# Relay.net
KiCad netlist of a schematic drawn in Altium Designer
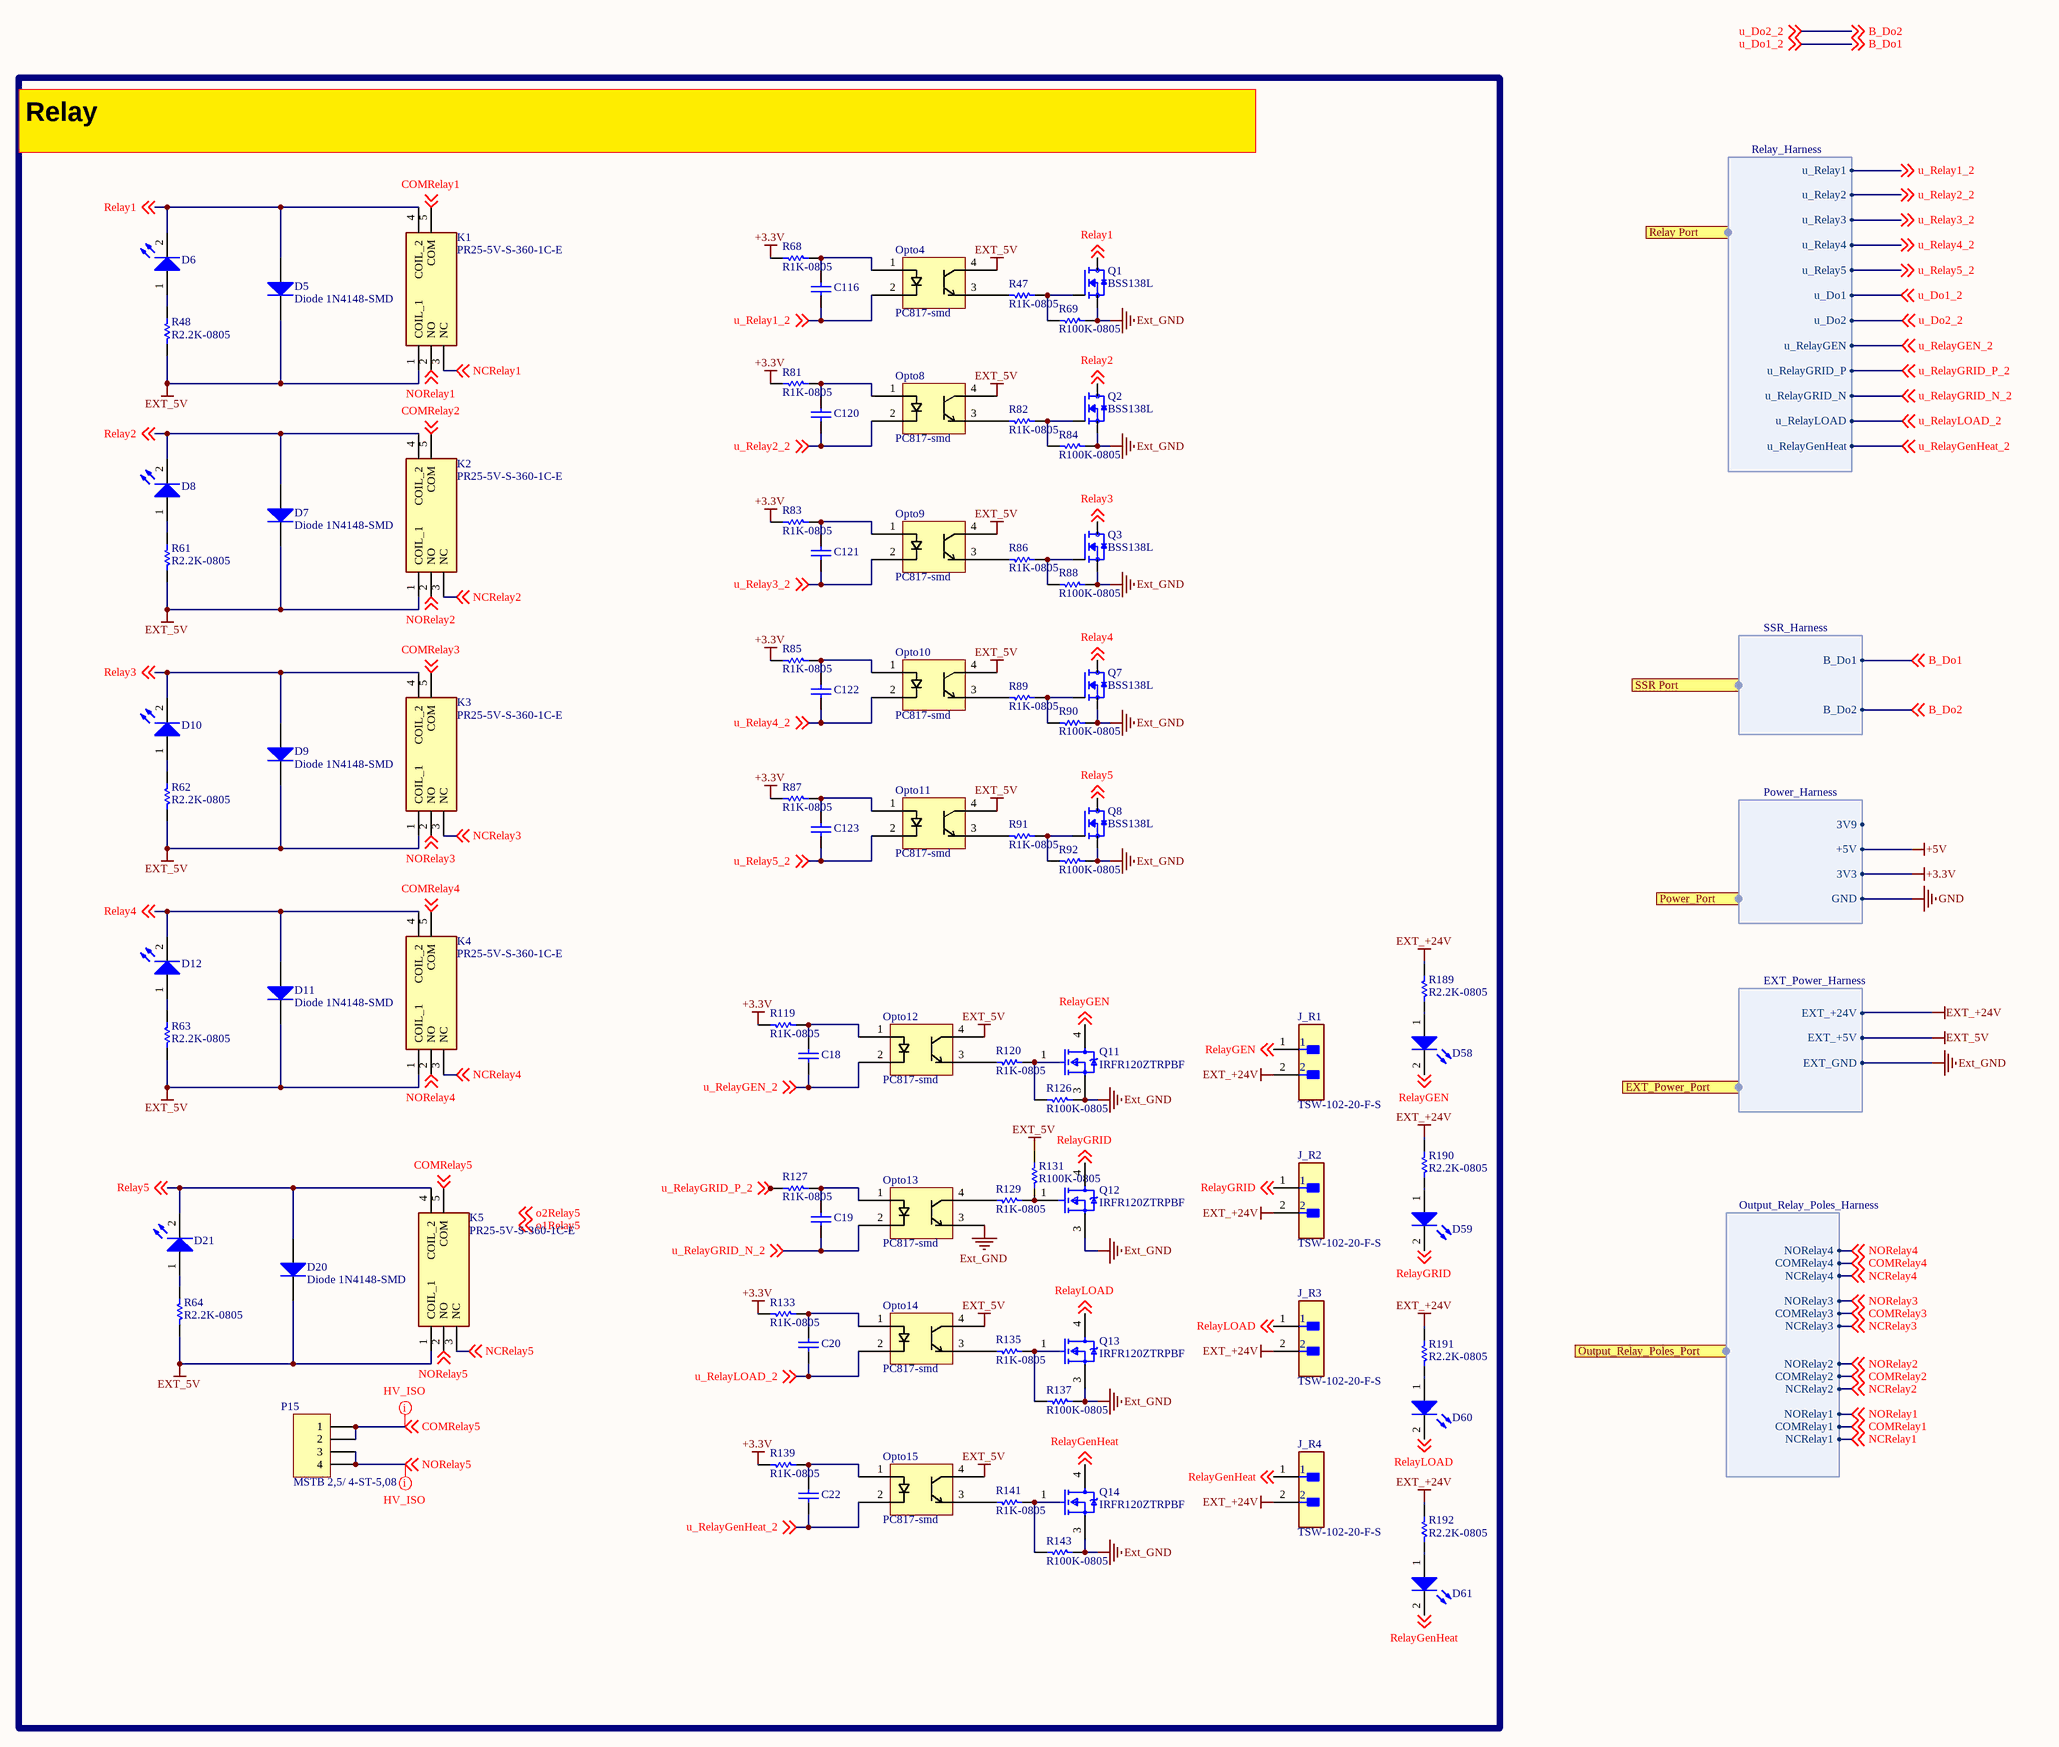
[diagram p0: Relay.SchDoc]

(export (version "E")
  (design (tool "Eeschema 10.0.6"))
  (components
    (comp (ref "C18")
      (value "~")
      (footprint "CRF06031")
      (description "Capacitor")
      (fields (field (name "DIGI-KEY_PART_NUMBER") "490-4789-1-ND"))
      (libsource (lib "Miscellaneous Devices") (part "Cap"))
    )
    (comp (ref "C19")
      (value "~")
      (footprint "CRF06031")
      (description "Capacitor")
      (fields (field (name "DIGI-KEY_PART_NUMBER") "490-4789-1-ND"))
      (libsource (lib "Miscellaneous Devices") (part "Cap"))
    )
    (comp (ref "C20")
      (value "~")
      (footprint "CRF06031")
      (description "Capacitor")
      (fields (field (name "DIGI-KEY_PART_NUMBER") "490-4789-1-ND"))
      (libsource (lib "Miscellaneous Devices") (part "Cap"))
    )
    (comp (ref "C22")
      (value "~")
      (footprint "CRF06031")
      (description "Capacitor")
      (fields (field (name "DIGI-KEY_PART_NUMBER") "490-4789-1-ND"))
      (libsource (lib "Miscellaneous Devices") (part "Cap"))
    )
    (comp (ref "C116")
      (value "~")
      (footprint "CRF06031")
      (description "Capacitor")
      (fields (field (name "DIGI-KEY_PART_NUMBER") "490-4789-1-ND"))
      (libsource (lib "Miscellaneous Devices") (part "Cap"))
    )
    (comp (ref "C120")
      (value "~")
      (footprint "CRF06031")
      (description "Capacitor")
      (fields (field (name "DIGI-KEY_PART_NUMBER") "490-4789-1-ND"))
      (libsource (lib "Miscellaneous Devices") (part "Cap"))
    )
    (comp (ref "C121")
      (value "~")
      (footprint "CRF06031")
      (description "Capacitor")
      (fields (field (name "DIGI-KEY_PART_NUMBER") "490-4789-1-ND"))
      (libsource (lib "Miscellaneous Devices") (part "Cap"))
    )
    (comp (ref "C122")
      (value "~")
      (footprint "CRF06031")
      (description "Capacitor")
      (fields (field (name "DIGI-KEY_PART_NUMBER") "490-4789-1-ND"))
      (libsource (lib "Miscellaneous Devices") (part "Cap"))
    )
    (comp (ref "C123")
      (value "~")
      (footprint "CRF06031")
      (description "Capacitor")
      (fields (field (name "DIGI-KEY_PART_NUMBER") "490-4789-1-ND"))
      (libsource (lib "Miscellaneous Devices") (part "Cap"))
    )
    (comp (ref "D5")
      (value "Diode 1N4148-SMD")
      (footprint "d1206")
      (description "1 Amp Fast Recovery Rectifier")
      (fields (field (name "DIGI-KEY_PART_NUMBER") "1N4148WSFSTR-ND"))
      (libsource (lib "Miscellaneous Devices") (part "Diode 1N4934"))
    )
    (comp (ref "D6")
      (value "LED_0805_green")
      (footprint "0805-LED")
      (libsource (lib "HosseinLib") (part "LED_0805"))
    )
    (comp (ref "D7")
      (value "Diode 1N4148-SMD")
      (footprint "d1206")
      (description "1 Amp Fast Recovery Rectifier")
      (fields (field (name "DIGI-KEY_PART_NUMBER") "1N4148WSFSTR-ND"))
      (libsource (lib "Miscellaneous Devices") (part "Diode 1N4934"))
    )
    (comp (ref "D8")
      (value "LED_0805_green")
      (footprint "0805-LED")
      (libsource (lib "HosseinLib") (part "LED_0805"))
    )
    (comp (ref "D9")
      (value "Diode 1N4148-SMD")
      (footprint "d1206")
      (description "1 Amp Fast Recovery Rectifier")
      (fields (field (name "DIGI-KEY_PART_NUMBER") "1N4148WSFSTR-ND"))
      (libsource (lib "Miscellaneous Devices") (part "Diode 1N4934"))
    )
    (comp (ref "D10")
      (value "LED_0805_green")
      (footprint "0805-LED")
      (libsource (lib "HosseinLib") (part "LED_0805"))
    )
    (comp (ref "D11")
      (value "Diode 1N4148-SMD")
      (footprint "d1206")
      (description "1 Amp Fast Recovery Rectifier")
      (fields (field (name "DIGI-KEY_PART_NUMBER") "1N4148WSFSTR-ND"))
      (libsource (lib "Miscellaneous Devices") (part "Diode 1N4934"))
    )
    (comp (ref "D12")
      (value "LED_0805_green")
      (footprint "0805-LED")
      (libsource (lib "HosseinLib") (part "LED_0805"))
    )
    (comp (ref "D20")
      (value "Diode 1N4148-SMD")
      (footprint "d1206")
      (description "1 Amp Fast Recovery Rectifier")
      (fields (field (name "DIGI-KEY_PART_NUMBER") "1N4148WSFSTR-ND"))
      (libsource (lib "Miscellaneous Devices") (part "Diode 1N4934"))
    )
    (comp (ref "D21")
      (value "LED_0805_green")
      (footprint "0805-LED")
      (libsource (lib "HosseinLib") (part "LED_0805"))
    )
    (comp (ref "D58")
      (value "LED_0805_green")
      (footprint "0805-LED")
      (libsource (lib "HosseinLib") (part "LED_0805"))
    )
    (comp (ref "D59")
      (value "LED_0805_green")
      (footprint "0805-LED")
      (libsource (lib "HosseinLib") (part "LED_0805"))
    )
    (comp (ref "D60")
      (value "LED_0805_green")
      (footprint "0805-LED")
      (libsource (lib "HosseinLib") (part "LED_0805"))
    )
    (comp (ref "D61")
      (value "LED_0805_green")
      (footprint "0805-LED")
      (libsource (lib "HosseinLib") (part "LED_0805"))
    )
    (comp (ref "J_R1")
      (value "TSW-102-20-F-S")
      (footprint "FP-TSW-102-12-T-S-MFG")
      (description "CONN HEADER VERT 2POS 2.54MM")
      (fields (field (name "DIGI-KEY_PART_NUMBER") "TSW-102-20-F-S-ND"))
      (libsource (lib "Components - 15.12.24 - 09.04") (part "CMP-02766-001444-1"))
    )
    (comp (ref "J_R2")
      (value "TSW-102-20-F-S")
      (footprint "FP-TSW-102-12-T-S-MFG")
      (description "CONN HEADER VERT 2POS 2.54MM")
      (fields (field (name "DIGI-KEY_PART_NUMBER") "TSW-102-20-F-S-ND"))
      (libsource (lib "Components - 15.12.24 - 09.04") (part "CMP-02766-001444-1"))
    )
    (comp (ref "J_R3")
      (value "TSW-102-20-F-S")
      (footprint "FP-TSW-102-12-T-S-MFG")
      (description "CONN HEADER VERT 2POS 2.54MM")
      (fields (field (name "DIGI-KEY_PART_NUMBER") "TSW-102-20-F-S-ND"))
      (libsource (lib "Components - 15.12.24 - 09.04") (part "CMP-02766-001444-1"))
    )
    (comp (ref "J_R4")
      (value "TSW-102-20-F-S")
      (footprint "FP-TSW-102-12-T-S-MFG")
      (description "CONN HEADER VERT 2POS 2.54MM")
      (fields (field (name "DIGI-KEY_PART_NUMBER") "TSW-102-20-F-S-ND"))
      (libsource (lib "Components - 15.12.24 - 09.04") (part "CMP-02766-001444-1"))
    )
    (comp (ref "K1")
      (value "PR25-5V-S-360-1C-E")
      (footprint "SamacSys:PR255VS3601CE")
      (description "Relay or Contactor")
      (fields
        (field (name "MOUSER PART NUMBER") "179-PR255VS3601CE")
        (field (name "DIGI-KEY_PART_NUMBER") "2223-PR25-5V-S-360-1C-E-ND")
      )
      (libsource (lib "*") (part "PR25-5V-S-360-1C-E"))
    )
    (comp (ref "K2")
      (value "PR25-5V-S-360-1C-E")
      (footprint "SamacSys:PR255VS3601CE")
      (description "Relay or Contactor")
      (fields
        (field (name "MOUSER PART NUMBER") "179-PR255VS3601CE")
        (field (name "DIGI-KEY_PART_NUMBER") "2223-PR25-5V-S-360-1C-E-ND")
      )
      (libsource (lib "*") (part "PR25-5V-S-360-1C-E"))
    )
    (comp (ref "K3")
      (value "PR25-5V-S-360-1C-E")
      (footprint "SamacSys:PR255VS3601CE")
      (description "Relay or Contactor")
      (fields
        (field (name "MOUSER PART NUMBER") "179-PR255VS3601CE")
        (field (name "DIGI-KEY_PART_NUMBER") "2223-PR25-5V-S-360-1C-E-ND")
      )
      (libsource (lib "*") (part "PR25-5V-S-360-1C-E"))
    )
    (comp (ref "K4")
      (value "PR25-5V-S-360-1C-E")
      (footprint "SamacSys:PR255VS3601CE")
      (description "Relay or Contactor")
      (fields
        (field (name "MOUSER PART NUMBER") "179-PR255VS3601CE")
        (field (name "DIGI-KEY_PART_NUMBER") "2223-PR25-5V-S-360-1C-E-ND")
      )
      (libsource (lib "*") (part "PR25-5V-S-360-1C-E"))
    )
    (comp (ref "K5")
      (value "PR25-5V-S-360-1C-E")
      (footprint "SamacSys:PR255VS3601CE")
      (description "Relay or Contactor")
      (fields
        (field (name "MOUSER PART NUMBER") "179-PR255VS3601CE")
        (field (name "DIGI-KEY_PART_NUMBER") "2223-PR25-5V-S-360-1C-E-ND")
      )
      (libsource (lib "*") (part "PR25-5V-S-360-1C-E"))
    )
    (comp (ref "Opto4")
      (value "PC817-smd")
      (footprint "PC817_SMD1")
      (fields (field (name "DIGI-KEY_PART_NUMBER") "2007-APC-817D1-SLTR-ND"))
      (libsource (lib "Almas Co") (part "PC817"))
    )
    (comp (ref "Opto8")
      (value "PC817-smd")
      (footprint "PC817_SMD1")
      (fields (field (name "DIGI-KEY_PART_NUMBER") "2007-APC-817D1-SLTR-ND"))
      (libsource (lib "Almas Co") (part "PC817"))
    )
    (comp (ref "Opto9")
      (value "PC817-smd")
      (footprint "PC817_SMD1")
      (fields (field (name "DIGI-KEY_PART_NUMBER") "2007-APC-817D1-SLTR-ND"))
      (libsource (lib "Almas Co") (part "PC817"))
    )
    (comp (ref "Opto10")
      (value "PC817-smd")
      (footprint "PC817_SMD1")
      (fields (field (name "DIGI-KEY_PART_NUMBER") "2007-APC-817D1-SLTR-ND"))
      (libsource (lib "Almas Co") (part "PC817"))
    )
    (comp (ref "Opto11")
      (value "PC817-smd")
      (footprint "PC817_SMD1")
      (fields (field (name "DIGI-KEY_PART_NUMBER") "2007-APC-817D1-SLTR-ND"))
      (libsource (lib "Almas Co") (part "PC817"))
    )
    (comp (ref "Opto12")
      (value "PC817-smd")
      (footprint "PC817_SMD1")
      (fields (field (name "DIGI-KEY_PART_NUMBER") "2007-APC-817D1-SLTR-ND"))
      (libsource (lib "Almas Co") (part "PC817"))
    )
    (comp (ref "Opto13")
      (value "PC817-smd")
      (footprint "PC817_SMD1")
      (fields (field (name "DIGI-KEY_PART_NUMBER") "2007-APC-817D1-SLTR-ND"))
      (libsource (lib "Almas Co") (part "PC817"))
    )
    (comp (ref "Opto14")
      (value "PC817-smd")
      (footprint "PC817_SMD1")
      (fields (field (name "DIGI-KEY_PART_NUMBER") "2007-APC-817D1-SLTR-ND"))
      (libsource (lib "Almas Co") (part "PC817"))
    )
    (comp (ref "Opto15")
      (value "PC817-smd")
      (footprint "PC817_SMD1")
      (fields (field (name "DIGI-KEY_PART_NUMBER") "2007-APC-817D1-SLTR-ND"))
      (libsource (lib "Almas Co") (part "PC817"))
    )
    (comp (ref "P15")
      (value "MSTB 2,5/ 4-ST-5,08")
      (footprint "MSTB 2,5/4-G-5,08")
      (description "Conn Phonix,4 Pitch: 5.08 mm")
      (fields (field (name "DIGI-KEY_PART_NUMBER") "277-1108-ND"))
      (libsource (lib "chilla bord") (part "Header 4"))
    )
    (comp (ref "Q1")
      (value "BSS138L")
      (footprint "BSS138L")
      (description "smd")
      (fields (field (name "MF") "ON Semiconductor") (field (name "DIGI-KEY_PART_NUMBER") "BSS138LTR-ND"))
      (libsource (lib "BSS138L") (part "BSS138L"))
    )
    (comp (ref "Q2")
      (value "BSS138L")
      (footprint "BSS138L")
      (description "smd")
      (fields (field (name "MF") "ON Semiconductor") (field (name "DIGI-KEY_PART_NUMBER") "BSS138LTR-ND"))
      (libsource (lib "BSS138L") (part "BSS138L"))
    )
    (comp (ref "Q3")
      (value "BSS138L")
      (footprint "BSS138L")
      (description "smd")
      (fields (field (name "MF") "ON Semiconductor") (field (name "DIGI-KEY_PART_NUMBER") "BSS138LTR-ND"))
      (libsource (lib "BSS138L") (part "BSS138L"))
    )
    (comp (ref "Q7")
      (value "BSS138L")
      (footprint "BSS138L")
      (description "smd")
      (fields (field (name "MF") "ON Semiconductor") (field (name "DIGI-KEY_PART_NUMBER") "BSS138LTR-ND"))
      (libsource (lib "BSS138L") (part "BSS138L"))
    )
    (comp (ref "Q8")
      (value "BSS138L")
      (footprint "BSS138L")
      (description "smd")
      (fields (field (name "MF") "ON Semiconductor") (field (name "DIGI-KEY_PART_NUMBER") "BSS138LTR-ND"))
      (libsource (lib "BSS138L") (part "BSS138L"))
    )
    (comp (ref "Q11")
      (value "IRFR120ZTRPBF")
      (footprint "FP-PG-TO252-3-MFG")
      (description "MOSFET N-CH 100V 8.7A DPAK")
      (fields (field (name "DIGI-KEY_PART_NUMBER") "IRFR120ZTRPBFTR-ND"))
      (libsource (lib "Altium Content Vault") (part "880dca94e4e73acafd9c8cab4fdbffa"))
    )
    (comp (ref "Q12")
      (value "IRFR120ZTRPBF")
      (footprint "FP-PG-TO252-3-MFG")
      (description "MOSFET N-CH 100V 8.7A DPAK")
      (fields (field (name "DIGI-KEY_PART_NUMBER") "IRFR120ZTRPBFTR-ND"))
      (libsource (lib "Altium Content Vault") (part "880dca94e4e73acafd9c8cab4fdbffa"))
    )
    (comp (ref "Q13")
      (value "IRFR120ZTRPBF")
      (footprint "FP-PG-TO252-3-MFG")
      (description "MOSFET N-CH 100V 8.7A DPAK")
      (fields (field (name "DIGI-KEY_PART_NUMBER") "IRFR120ZTRPBFTR-ND"))
      (libsource (lib "Altium Content Vault") (part "880dca94e4e73acafd9c8cab4fdbffa"))
    )
    (comp (ref "Q14")
      (value "IRFR120ZTRPBF")
      (footprint "FP-PG-TO252-3-MFG")
      (description "MOSFET N-CH 100V 8.7A DPAK")
      (fields (field (name "DIGI-KEY_PART_NUMBER") "IRFR120ZTRPBFTR-ND"))
      (libsource (lib "Altium Content Vault") (part "880dca94e4e73acafd9c8cab4fdbffa"))
    )
    (comp (ref "R47")
      (value "R1K-0805")
      (footprint "CRF06031")
      (description "Resistor")
      (fields (field (name "DIGI-KEY_PART_NUMBER") "311-1.00KCRTR-ND"))
      (libsource (lib "Miscellaneous Devices") (part "Res1"))
    )
    (comp (ref "R48")
      (value "R2.2K-0805")
      (footprint "CRF06031")
      (description "Resistor")
      (fields (field (name "DIGI-KEY_PART_NUMBER") "311-2.20KCRTR-ND"))
      (libsource (lib "Miscellaneous Devices") (part "Res1"))
    )
    (comp (ref "R61")
      (value "R2.2K-0805")
      (footprint "CRF06031")
      (description "Resistor")
      (fields (field (name "DIGI-KEY_PART_NUMBER") "311-2.20KCRTR-ND"))
      (libsource (lib "Miscellaneous Devices") (part "Res1"))
    )
    (comp (ref "R62")
      (value "R2.2K-0805")
      (footprint "CRF06031")
      (description "Resistor")
      (fields (field (name "DIGI-KEY_PART_NUMBER") "311-2.20KCRTR-ND"))
      (libsource (lib "Miscellaneous Devices") (part "Res1"))
    )
    (comp (ref "R63")
      (value "R2.2K-0805")
      (footprint "CRF06031")
      (description "Resistor")
      (fields (field (name "DIGI-KEY_PART_NUMBER") "311-2.20KCRTR-ND"))
      (libsource (lib "Miscellaneous Devices") (part "Res1"))
    )
    (comp (ref "R64")
      (value "R2.2K-0805")
      (footprint "CRF06031")
      (description "Resistor")
      (fields (field (name "DIGI-KEY_PART_NUMBER") "311-2.20KCRTR-ND"))
      (libsource (lib "Miscellaneous Devices") (part "Res1"))
    )
    (comp (ref "R68")
      (value "R1K-0805")
      (footprint "CRF06031")
      (description "Resistor")
      (fields (field (name "DIGI-KEY_PART_NUMBER") "311-1.00KCRTR-ND"))
      (libsource (lib "Miscellaneous Devices") (part "Res1"))
    )
    (comp (ref "R69")
      (value "R100K-0805")
      (footprint "CRF06031")
      (description "Resistor")
      (fields (field (name "DIGI-KEY_PART_NUMBER") "311-100KCRTR-ND"))
      (libsource (lib "Miscellaneous Devices") (part "Res1"))
    )
    (comp (ref "R81")
      (value "R1K-0805")
      (footprint "CRF06031")
      (description "Resistor")
      (fields (field (name "DIGI-KEY_PART_NUMBER") "311-1.00KCRTR-ND"))
      (libsource (lib "Miscellaneous Devices") (part "Res1"))
    )
    (comp (ref "R82")
      (value "R1K-0805")
      (footprint "CRF06031")
      (description "Resistor")
      (fields (field (name "DIGI-KEY_PART_NUMBER") "311-1.00KCRTR-ND"))
      (libsource (lib "Miscellaneous Devices") (part "Res1"))
    )
    (comp (ref "R83")
      (value "R1K-0805")
      (footprint "CRF06031")
      (description "Resistor")
      (fields (field (name "DIGI-KEY_PART_NUMBER") "311-1.00KCRTR-ND"))
      (libsource (lib "Miscellaneous Devices") (part "Res1"))
    )
    (comp (ref "R84")
      (value "R100K-0805")
      (footprint "CRF06031")
      (description "Resistor")
      (fields (field (name "DIGI-KEY_PART_NUMBER") "311-100KCRTR-ND"))
      (libsource (lib "Miscellaneous Devices") (part "Res1"))
    )
    (comp (ref "R85")
      (value "R1K-0805")
      (footprint "CRF06031")
      (description "Resistor")
      (fields (field (name "DIGI-KEY_PART_NUMBER") "311-1.00KCRTR-ND"))
      (libsource (lib "Miscellaneous Devices") (part "Res1"))
    )
    (comp (ref "R86")
      (value "R1K-0805")
      (footprint "CRF06031")
      (description "Resistor")
      (fields (field (name "DIGI-KEY_PART_NUMBER") "311-1.00KCRTR-ND"))
      (libsource (lib "Miscellaneous Devices") (part "Res1"))
    )
    (comp (ref "R87")
      (value "R1K-0805")
      (footprint "CRF06031")
      (description "Resistor")
      (fields (field (name "DIGI-KEY_PART_NUMBER") "311-1.00KCRTR-ND"))
      (libsource (lib "Miscellaneous Devices") (part "Res1"))
    )
    (comp (ref "R88")
      (value "R100K-0805")
      (footprint "CRF06031")
      (description "Resistor")
      (fields (field (name "DIGI-KEY_PART_NUMBER") "311-100KCRTR-ND"))
      (libsource (lib "Miscellaneous Devices") (part "Res1"))
    )
    (comp (ref "R89")
      (value "R1K-0805")
      (footprint "CRF06031")
      (description "Resistor")
      (fields (field (name "DIGI-KEY_PART_NUMBER") "311-1.00KCRTR-ND"))
      (libsource (lib "Miscellaneous Devices") (part "Res1"))
    )
    (comp (ref "R90")
      (value "R100K-0805")
      (footprint "CRF06031")
      (description "Resistor")
      (fields (field (name "DIGI-KEY_PART_NUMBER") "311-100KCRTR-ND"))
      (libsource (lib "Miscellaneous Devices") (part "Res1"))
    )
    (comp (ref "R91")
      (value "R1K-0805")
      (footprint "CRF06031")
      (description "Resistor")
      (fields (field (name "DIGI-KEY_PART_NUMBER") "311-1.00KCRTR-ND"))
      (libsource (lib "Miscellaneous Devices") (part "Res1"))
    )
    (comp (ref "R92")
      (value "R100K-0805")
      (footprint "CRF06031")
      (description "Resistor")
      (fields (field (name "DIGI-KEY_PART_NUMBER") "311-100KCRTR-ND"))
      (libsource (lib "Miscellaneous Devices") (part "Res1"))
    )
    (comp (ref "R119")
      (value "R1K-0805")
      (footprint "CRF06031")
      (description "Resistor")
      (fields (field (name "DIGI-KEY_PART_NUMBER") "311-1.00KCRTR-ND"))
      (libsource (lib "Miscellaneous Devices") (part "Res1"))
    )
    (comp (ref "R120")
      (value "R1K-0805")
      (footprint "CRF06031")
      (description "Resistor")
      (fields (field (name "DIGI-KEY_PART_NUMBER") "311-1.00KCRTR-ND"))
      (libsource (lib "Miscellaneous Devices") (part "Res1"))
    )
    (comp (ref "R126")
      (value "R100K-0805")
      (footprint "CRF06031")
      (description "Resistor")
      (fields (field (name "DIGI-KEY_PART_NUMBER") "311-100KCRTR-ND"))
      (libsource (lib "Miscellaneous Devices") (part "Res1"))
    )
    (comp (ref "R127")
      (value "R1K-0805")
      (footprint "CRF06031")
      (description "Resistor")
      (fields (field (name "DIGI-KEY_PART_NUMBER") "311-1.00KCRTR-ND"))
      (libsource (lib "Miscellaneous Devices") (part "Res1"))
    )
    (comp (ref "R129")
      (value "R1K-0805")
      (footprint "CRF06031")
      (description "Resistor")
      (fields (field (name "DIGI-KEY_PART_NUMBER") "311-1.00KCRTR-ND"))
      (libsource (lib "Miscellaneous Devices") (part "Res1"))
    )
    (comp (ref "R131")
      (value "R100K-0805")
      (footprint "CRF06031")
      (description "Resistor")
      (fields (field (name "DIGI-KEY_PART_NUMBER") "311-100KCRTR-ND"))
      (libsource (lib "Miscellaneous Devices") (part "Res1"))
    )
    (comp (ref "R133")
      (value "R1K-0805")
      (footprint "CRF06031")
      (description "Resistor")
      (fields (field (name "DIGI-KEY_PART_NUMBER") "311-1.00KCRTR-ND"))
      (libsource (lib "Miscellaneous Devices") (part "Res1"))
    )
    (comp (ref "R135")
      (value "R1K-0805")
      (footprint "CRF06031")
      (description "Resistor")
      (fields (field (name "DIGI-KEY_PART_NUMBER") "311-1.00KCRTR-ND"))
      (libsource (lib "Miscellaneous Devices") (part "Res1"))
    )
    (comp (ref "R137")
      (value "R100K-0805")
      (footprint "CRF06031")
      (description "Resistor")
      (fields (field (name "DIGI-KEY_PART_NUMBER") "311-100KCRTR-ND"))
      (libsource (lib "Miscellaneous Devices") (part "Res1"))
    )
    (comp (ref "R139")
      (value "R1K-0805")
      (footprint "CRF06031")
      (description "Resistor")
      (fields (field (name "DIGI-KEY_PART_NUMBER") "311-1.00KCRTR-ND"))
      (libsource (lib "Miscellaneous Devices") (part "Res1"))
    )
    (comp (ref "R141")
      (value "R1K-0805")
      (footprint "CRF06031")
      (description "Resistor")
      (fields (field (name "DIGI-KEY_PART_NUMBER") "311-1.00KCRTR-ND"))
      (libsource (lib "Miscellaneous Devices") (part "Res1"))
    )
    (comp (ref "R143")
      (value "R100K-0805")
      (footprint "CRF06031")
      (description "Resistor")
      (fields (field (name "DIGI-KEY_PART_NUMBER") "311-100KCRTR-ND"))
      (libsource (lib "Miscellaneous Devices") (part "Res1"))
    )
    (comp (ref "R189")
      (value "R2.2K-0805")
      (footprint "CRF06031")
      (description "Resistor")
      (fields (field (name "DIGI-KEY_PART_NUMBER") "311-2.20KCRTR-ND"))
      (libsource (lib "Miscellaneous Devices") (part "Res1"))
    )
    (comp (ref "R190")
      (value "R2.2K-0805")
      (footprint "CRF06031")
      (description "Resistor")
      (fields (field (name "DIGI-KEY_PART_NUMBER") "311-2.20KCRTR-ND"))
      (libsource (lib "Miscellaneous Devices") (part "Res1"))
    )
    (comp (ref "R191")
      (value "R2.2K-0805")
      (footprint "CRF06031")
      (description "Resistor")
      (fields (field (name "DIGI-KEY_PART_NUMBER") "311-2.20KCRTR-ND"))
      (libsource (lib "Miscellaneous Devices") (part "Res1"))
    )
    (comp (ref "R192")
      (value "R2.2K-0805")
      (footprint "CRF06031")
      (description "Resistor")
      (fields (field (name "DIGI-KEY_PART_NUMBER") "311-2.20KCRTR-ND"))
      (libsource (lib "Miscellaneous Devices") (part "Res1"))
    )
  )
  (nets
    (net (code "6") (name "+3.3V") (class "Default")
      (node (ref "R119") (pin "2") (pinfunction "2_2") (pintype "passive"))
      (node (ref "R133") (pin "2") (pinfunction "2_2") (pintype "passive"))
      (node (ref "R139") (pin "2") (pinfunction "2_2") (pintype "passive"))
      (node (ref "R68") (pin "2") (pinfunction "2_2") (pintype "passive"))
      (node (ref "R81") (pin "2") (pinfunction "2_2") (pintype "passive"))
      (node (ref "R83") (pin "2") (pinfunction "2_2") (pintype "passive"))
      (node (ref "R85") (pin "2") (pinfunction "2_2") (pintype "passive"))
      (node (ref "R87") (pin "2") (pinfunction "2_2") (pintype "passive"))
    )
    (net (code "15") (name "COMRelay1") (class "Default")
      (node (ref "K1") (pin "5") (pinfunction "COM_5") (pintype "passive"))
    )
    (net (code "16") (name "COMRelay2") (class "Default")
      (node (ref "K2") (pin "5") (pinfunction "COM_5") (pintype "passive"))
    )
    (net (code "17") (name "COMRelay3") (class "Default")
      (node (ref "K3") (pin "5") (pinfunction "COM_5") (pintype "passive"))
    )
    (net (code "18") (name "COMRelay4") (class "Default")
      (node (ref "K4") (pin "5") (pinfunction "COM_5") (pintype "passive"))
    )
    (net (code "19") (name "COMRelay5") (class "Default")
      (node (ref "K5") (pin "5") (pinfunction "COM_5") (pintype "passive"))
      (node (ref "P15") (pin "1") (pinfunction "1_1") (pintype "passive"))
      (node (ref "P15") (pin "2") (pinfunction "2_2") (pintype "passive"))
    )
    (net (code "20") (name "EXT_+24V") (class "Default")
      (node (ref "J_R1") (pin "2") (pinfunction "2_2") (pintype "passive"))
      (node (ref "J_R2") (pin "2") (pinfunction "2_2") (pintype "passive"))
      (node (ref "J_R3") (pin "2") (pinfunction "2_2") (pintype "passive"))
      (node (ref "J_R4") (pin "2") (pinfunction "2_2") (pintype "passive"))
      (node (ref "R189") (pin "2") (pinfunction "2_2") (pintype "passive"))
      (node (ref "R190") (pin "2") (pinfunction "2_2") (pintype "passive"))
      (node (ref "R191") (pin "2") (pinfunction "2_2") (pintype "passive"))
      (node (ref "R192") (pin "2") (pinfunction "2_2") (pintype "passive"))
    )
    (net (code "21") (name "EXT_5V") (class "Default")
      (node (ref "D11") (pin "2") (pinfunction "K_2") (pintype "passive"))
      (node (ref "D20") (pin "2") (pinfunction "K_2") (pintype "passive"))
      (node (ref "D5") (pin "2") (pinfunction "K_2") (pintype "passive"))
      (node (ref "D7") (pin "2") (pinfunction "K_2") (pintype "passive"))
      (node (ref "D9") (pin "2") (pinfunction "K_2") (pintype "passive"))
      (node (ref "K1") (pin "1") (pinfunction "COIL_1_1") (pintype "passive"))
      (node (ref "K2") (pin "1") (pinfunction "COIL_1_1") (pintype "passive"))
      (node (ref "K3") (pin "1") (pinfunction "COIL_1_1") (pintype "passive"))
      (node (ref "K4") (pin "1") (pinfunction "COIL_1_1") (pintype "passive"))
      (node (ref "K5") (pin "1") (pinfunction "COIL_1_1") (pintype "passive"))
      (node (ref "Opto10") (pin "4") (pintype "passive"))
      (node (ref "Opto11") (pin "4") (pintype "passive"))
      (node (ref "Opto12") (pin "4") (pintype "passive"))
      (node (ref "Opto14") (pin "4") (pintype "passive"))
      (node (ref "Opto15") (pin "4") (pintype "passive"))
      (node (ref "Opto4") (pin "4") (pintype "passive"))
      (node (ref "Opto8") (pin "4") (pintype "passive"))
      (node (ref "Opto9") (pin "4") (pintype "passive"))
      (node (ref "R131") (pin "2") (pinfunction "2_2") (pintype "passive"))
      (node (ref "R48") (pin "2") (pinfunction "2_2") (pintype "passive"))
      (node (ref "R61") (pin "2") (pinfunction "2_2") (pintype "passive"))
      (node (ref "R62") (pin "2") (pinfunction "2_2") (pintype "passive"))
      (node (ref "R63") (pin "2") (pinfunction "2_2") (pintype "passive"))
      (node (ref "R64") (pin "2") (pinfunction "2_2") (pintype "passive"))
    )
    (net (code "22") (name "Ext_GND") (class "Default")
      (node (ref "Opto13") (pin "3") (pintype "passive"))
      (node (ref "Q1") (pin "S") (pinfunction "S_S") (pintype "passive"))
      (node (ref "Q11") (pin "3") (pinfunction "SOURCE_3") (pintype "passive"))
      (node (ref "Q12") (pin "3") (pinfunction "SOURCE_3") (pintype "passive"))
      (node (ref "Q13") (pin "3") (pinfunction "SOURCE_3") (pintype "passive"))
      (node (ref "Q14") (pin "3") (pinfunction "SOURCE_3") (pintype "passive"))
      (node (ref "Q2") (pin "S") (pinfunction "S_S") (pintype "passive"))
      (node (ref "Q3") (pin "S") (pinfunction "S_S") (pintype "passive"))
      (node (ref "Q7") (pin "S") (pinfunction "S_S") (pintype "passive"))
      (node (ref "Q8") (pin "S") (pinfunction "S_S") (pintype "passive"))
      (node (ref "R126") (pin "2") (pinfunction "2_2") (pintype "passive"))
      (node (ref "R137") (pin "2") (pinfunction "2_2") (pintype "passive"))
      (node (ref "R143") (pin "2") (pinfunction "2_2") (pintype "passive"))
      (node (ref "R69") (pin "2") (pinfunction "2_2") (pintype "passive"))
      (node (ref "R84") (pin "2") (pinfunction "2_2") (pintype "passive"))
      (node (ref "R88") (pin "2") (pinfunction "2_2") (pintype "passive"))
      (node (ref "R90") (pin "2") (pinfunction "2_2") (pintype "passive"))
      (node (ref "R92") (pin "2") (pinfunction "2_2") (pintype "passive"))
    )
    (net (code "24") (name "NCRelay1") (class "Default")
      (node (ref "K1") (pin "3") (pinfunction "NC_3") (pintype "passive"))
    )
    (net (code "25") (name "NCRelay2") (class "Default")
      (node (ref "K2") (pin "3") (pinfunction "NC_3") (pintype "passive"))
    )
    (net (code "26") (name "NCRelay3") (class "Default")
      (node (ref "K3") (pin "3") (pinfunction "NC_3") (pintype "passive"))
    )
    (net (code "27") (name "NCRelay4") (class "Default")
      (node (ref "K4") (pin "3") (pinfunction "NC_3") (pintype "passive"))
    )
    (net (code "28") (name "NCRelay5") (class "Default")
      (node (ref "K5") (pin "3") (pinfunction "NC_3") (pintype "passive"))
    )
    (net (code "29") (name "NORelay1") (class "Default")
      (node (ref "K1") (pin "2") (pinfunction "NO_2") (pintype "passive"))
    )
    (net (code "30") (name "NORelay2") (class "Default")
      (node (ref "K2") (pin "2") (pinfunction "NO_2") (pintype "passive"))
    )
    (net (code "31") (name "NORelay3") (class "Default")
      (node (ref "K3") (pin "2") (pinfunction "NO_2") (pintype "passive"))
    )
    (net (code "32") (name "NORelay4") (class "Default")
      (node (ref "K4") (pin "2") (pinfunction "NO_2") (pintype "passive"))
    )
    (net (code "33") (name "NORelay5") (class "Default")
      (node (ref "K5") (pin "2") (pinfunction "NO_2") (pintype "passive"))
      (node (ref "P15") (pin "3") (pinfunction "3_3") (pintype "passive"))
      (node (ref "P15") (pin "4") (pinfunction "4_4") (pintype "passive"))
    )
    (net (code "34") (name "Net-(C18-Pad2)") (class "Default")
      (node (ref "C18") (pin "2") (pinfunction "2_2") (pintype "passive"))
      (node (ref "Opto12") (pin "1") (pintype "passive"))
      (node (ref "R119") (pin "1") (pinfunction "1_1") (pintype "passive"))
    )
    (net (code "35") (name "Net-(C19-Pad2)") (class "Default")
      (node (ref "C19") (pin "2") (pinfunction "2_2") (pintype "passive"))
      (node (ref "Opto13") (pin "1") (pintype "passive"))
      (node (ref "R127") (pin "1") (pinfunction "1_1") (pintype "passive"))
    )
    (net (code "36") (name "Net-(C20-Pad2)") (class "Default")
      (node (ref "C20") (pin "2") (pinfunction "2_2") (pintype "passive"))
      (node (ref "Opto14") (pin "1") (pintype "passive"))
      (node (ref "R133") (pin "1") (pinfunction "1_1") (pintype "passive"))
    )
    (net (code "37") (name "Net-(C22-Pad2)") (class "Default")
      (node (ref "C22") (pin "2") (pinfunction "2_2") (pintype "passive"))
      (node (ref "Opto15") (pin "1") (pintype "passive"))
      (node (ref "R139") (pin "1") (pinfunction "1_1") (pintype "passive"))
    )
    (net (code "38") (name "Net-(C116-Pad2)") (class "Default")
      (node (ref "C116") (pin "2") (pinfunction "2_2") (pintype "passive"))
      (node (ref "Opto4") (pin "1") (pintype "passive"))
      (node (ref "R68") (pin "1") (pinfunction "1_1") (pintype "passive"))
    )
    (net (code "39") (name "Net-(C120-Pad2)") (class "Default")
      (node (ref "C120") (pin "2") (pinfunction "2_2") (pintype "passive"))
      (node (ref "Opto8") (pin "1") (pintype "passive"))
      (node (ref "R81") (pin "1") (pinfunction "1_1") (pintype "passive"))
    )
    (net (code "40") (name "Net-(C121-Pad2)") (class "Default")
      (node (ref "C121") (pin "2") (pinfunction "2_2") (pintype "passive"))
      (node (ref "Opto9") (pin "1") (pintype "passive"))
      (node (ref "R83") (pin "1") (pinfunction "1_1") (pintype "passive"))
    )
    (net (code "41") (name "Net-(C122-Pad2)") (class "Default")
      (node (ref "C122") (pin "2") (pinfunction "2_2") (pintype "passive"))
      (node (ref "Opto10") (pin "1") (pintype "passive"))
      (node (ref "R85") (pin "1") (pinfunction "1_1") (pintype "passive"))
    )
    (net (code "42") (name "Net-(C123-Pad2)") (class "Default")
      (node (ref "C123") (pin "2") (pinfunction "2_2") (pintype "passive"))
      (node (ref "Opto11") (pin "1") (pintype "passive"))
      (node (ref "R87") (pin "1") (pinfunction "1_1") (pintype "passive"))
    )
    (net (code "43") (name "Net-(D6-A)") (class "Default")
      (node (ref "D6") (pin "1") (pinfunction "A_1") (pintype "passive"))
      (node (ref "R48") (pin "1") (pinfunction "1_1") (pintype "passive"))
    )
    (net (code "44") (name "Net-(D8-A)") (class "Default")
      (node (ref "D8") (pin "1") (pinfunction "A_1") (pintype "passive"))
      (node (ref "R61") (pin "1") (pinfunction "1_1") (pintype "passive"))
    )
    (net (code "45") (name "Net-(D10-A)") (class "Default")
      (node (ref "D10") (pin "1") (pinfunction "A_1") (pintype "passive"))
      (node (ref "R62") (pin "1") (pinfunction "1_1") (pintype "passive"))
    )
    (net (code "46") (name "Net-(D12-A)") (class "Default")
      (node (ref "D12") (pin "1") (pinfunction "A_1") (pintype "passive"))
      (node (ref "R63") (pin "1") (pinfunction "1_1") (pintype "passive"))
    )
    (net (code "47") (name "Net-(D21-A)") (class "Default")
      (node (ref "D21") (pin "1") (pinfunction "A_1") (pintype "passive"))
      (node (ref "R64") (pin "1") (pinfunction "1_1") (pintype "passive"))
    )
    (net (code "48") (name "Net-(D58-A)") (class "Default")
      (node (ref "D58") (pin "1") (pinfunction "A_1") (pintype "passive"))
      (node (ref "R189") (pin "1") (pinfunction "1_1") (pintype "passive"))
    )
    (net (code "49") (name "Net-(D59-A)") (class "Default")
      (node (ref "D59") (pin "1") (pinfunction "A_1") (pintype "passive"))
      (node (ref "R190") (pin "1") (pinfunction "1_1") (pintype "passive"))
    )
    (net (code "50") (name "Net-(D60-A)") (class "Default")
      (node (ref "D60") (pin "1") (pinfunction "A_1") (pintype "passive"))
      (node (ref "R191") (pin "1") (pinfunction "1_1") (pintype "passive"))
    )
    (net (code "51") (name "Net-(D61-A)") (class "Default")
      (node (ref "D61") (pin "1") (pinfunction "A_1") (pintype "passive"))
      (node (ref "R192") (pin "1") (pinfunction "1_1") (pintype "passive"))
    )
    (net (code "52") (name "Net-(Opto4-Pad3)") (class "Default")
      (node (ref "Opto4") (pin "3") (pintype "passive"))
      (node (ref "R47") (pin "2") (pinfunction "2_2") (pintype "passive"))
    )
    (net (code "53") (name "Net-(Opto8-Pad3)") (class "Default")
      (node (ref "Opto8") (pin "3") (pintype "passive"))
      (node (ref "R82") (pin "2") (pinfunction "2_2") (pintype "passive"))
    )
    (net (code "54") (name "Net-(Opto9-Pad3)") (class "Default")
      (node (ref "Opto9") (pin "3") (pintype "passive"))
      (node (ref "R86") (pin "2") (pinfunction "2_2") (pintype "passive"))
    )
    (net (code "55") (name "Net-(Opto10-Pad3)") (class "Default")
      (node (ref "Opto10") (pin "3") (pintype "passive"))
      (node (ref "R89") (pin "2") (pinfunction "2_2") (pintype "passive"))
    )
    (net (code "56") (name "Net-(Opto11-Pad3)") (class "Default")
      (node (ref "Opto11") (pin "3") (pintype "passive"))
      (node (ref "R91") (pin "2") (pinfunction "2_2") (pintype "passive"))
    )
    (net (code "57") (name "Net-(Opto12-Pad3)") (class "Default")
      (node (ref "Opto12") (pin "3") (pintype "passive"))
      (node (ref "R120") (pin "2") (pinfunction "2_2") (pintype "passive"))
    )
    (net (code "58") (name "Net-(Opto13-Pad4)") (class "Default")
      (node (ref "Opto13") (pin "4") (pintype "passive"))
      (node (ref "R129") (pin "2") (pinfunction "2_2") (pintype "passive"))
    )
    (net (code "59") (name "Net-(Opto14-Pad3)") (class "Default")
      (node (ref "Opto14") (pin "3") (pintype "passive"))
      (node (ref "R135") (pin "2") (pinfunction "2_2") (pintype "passive"))
    )
    (net (code "60") (name "Net-(Opto15-Pad3)") (class "Default")
      (node (ref "Opto15") (pin "3") (pintype "passive"))
      (node (ref "R141") (pin "2") (pinfunction "2_2") (pintype "passive"))
    )
    (net (code "61") (name "Net-(Q1-PadG)") (class "Default")
      (node (ref "Q1") (pin "G") (pinfunction "G_G") (pintype "passive"))
      (node (ref "R47") (pin "1") (pinfunction "1_1") (pintype "passive"))
      (node (ref "R69") (pin "1") (pinfunction "1_1") (pintype "passive"))
    )
    (net (code "62") (name "Net-(Q2-PadG)") (class "Default")
      (node (ref "Q2") (pin "G") (pinfunction "G_G") (pintype "passive"))
      (node (ref "R82") (pin "1") (pinfunction "1_1") (pintype "passive"))
      (node (ref "R84") (pin "1") (pinfunction "1_1") (pintype "passive"))
    )
    (net (code "63") (name "Net-(Q3-PadG)") (class "Default")
      (node (ref "Q3") (pin "G") (pinfunction "G_G") (pintype "passive"))
      (node (ref "R86") (pin "1") (pinfunction "1_1") (pintype "passive"))
      (node (ref "R88") (pin "1") (pinfunction "1_1") (pintype "passive"))
    )
    (net (code "64") (name "Net-(Q7-PadG)") (class "Default")
      (node (ref "Q7") (pin "G") (pinfunction "G_G") (pintype "passive"))
      (node (ref "R89") (pin "1") (pinfunction "1_1") (pintype "passive"))
      (node (ref "R90") (pin "1") (pinfunction "1_1") (pintype "passive"))
    )
    (net (code "65") (name "Net-(Q8-PadG)") (class "Default")
      (node (ref "Q8") (pin "G") (pinfunction "G_G") (pintype "passive"))
      (node (ref "R91") (pin "1") (pinfunction "1_1") (pintype "passive"))
      (node (ref "R92") (pin "1") (pinfunction "1_1") (pintype "passive"))
    )
    (net (code "66") (name "Net-(Q11-GATE)") (class "Default")
      (node (ref "Q11") (pin "1") (pinfunction "GATE_1") (pintype "passive"))
      (node (ref "R120") (pin "1") (pinfunction "1_1") (pintype "passive"))
      (node (ref "R126") (pin "1") (pinfunction "1_1") (pintype "passive"))
    )
    (net (code "67") (name "Net-(Q12-GATE)") (class "Default")
      (node (ref "Q12") (pin "1") (pinfunction "GATE_1") (pintype "passive"))
      (node (ref "R129") (pin "1") (pinfunction "1_1") (pintype "passive"))
      (node (ref "R131") (pin "1") (pinfunction "1_1") (pintype "passive"))
    )
    (net (code "68") (name "Net-(Q13-GATE)") (class "Default")
      (node (ref "Q13") (pin "1") (pinfunction "GATE_1") (pintype "passive"))
      (node (ref "R135") (pin "1") (pinfunction "1_1") (pintype "passive"))
      (node (ref "R137") (pin "1") (pinfunction "1_1") (pintype "passive"))
    )
    (net (code "69") (name "Net-(Q14-GATE)") (class "Default")
      (node (ref "Q14") (pin "1") (pinfunction "GATE_1") (pintype "passive"))
      (node (ref "R141") (pin "1") (pinfunction "1_1") (pintype "passive"))
      (node (ref "R143") (pin "1") (pinfunction "1_1") (pintype "passive"))
    )
    (net (code "70") (name "Relay1") (class "Default")
      (node (ref "D5") (pin "1") (pinfunction "A_1") (pintype "passive"))
      (node (ref "D6") (pin "2") (pinfunction "K_2") (pintype "passive"))
      (node (ref "K1") (pin "4") (pinfunction "COIL_2_4") (pintype "passive"))
      (node (ref "Q1") (pin "D") (pinfunction "D_D") (pintype "passive"))
    )
    (net (code "71") (name "Relay2") (class "Default")
      (node (ref "D7") (pin "1") (pinfunction "A_1") (pintype "passive"))
      (node (ref "D8") (pin "2") (pinfunction "K_2") (pintype "passive"))
      (node (ref "K2") (pin "4") (pinfunction "COIL_2_4") (pintype "passive"))
      (node (ref "Q2") (pin "D") (pinfunction "D_D") (pintype "passive"))
    )
    (net (code "72") (name "Relay3") (class "Default")
      (node (ref "D10") (pin "2") (pinfunction "K_2") (pintype "passive"))
      (node (ref "D9") (pin "1") (pinfunction "A_1") (pintype "passive"))
      (node (ref "K3") (pin "4") (pinfunction "COIL_2_4") (pintype "passive"))
      (node (ref "Q3") (pin "D") (pinfunction "D_D") (pintype "passive"))
    )
    (net (code "73") (name "Relay4") (class "Default")
      (node (ref "D11") (pin "1") (pinfunction "A_1") (pintype "passive"))
      (node (ref "D12") (pin "2") (pinfunction "K_2") (pintype "passive"))
      (node (ref "K4") (pin "4") (pinfunction "COIL_2_4") (pintype "passive"))
      (node (ref "Q7") (pin "D") (pinfunction "D_D") (pintype "passive"))
    )
    (net (code "74") (name "Relay5") (class "Default")
      (node (ref "D20") (pin "1") (pinfunction "A_1") (pintype "passive"))
      (node (ref "D21") (pin "2") (pinfunction "K_2") (pintype "passive"))
      (node (ref "K5") (pin "4") (pinfunction "COIL_2_4") (pintype "passive"))
      (node (ref "Q8") (pin "D") (pinfunction "D_D") (pintype "passive"))
    )
    (net (code "75") (name "RelayGEN") (class "Default")
      (node (ref "D58") (pin "2") (pinfunction "K_2") (pintype "passive"))
      (node (ref "J_R1") (pin "1") (pinfunction "1_1") (pintype "passive"))
      (node (ref "Q11") (pin "4") (pinfunction "DRAIN_4") (pintype "passive"))
    )
    (net (code "76") (name "RelayGRID") (class "Default")
      (node (ref "D59") (pin "2") (pinfunction "K_2") (pintype "passive"))
      (node (ref "J_R2") (pin "1") (pinfunction "1_1") (pintype "passive"))
      (node (ref "Q12") (pin "4") (pinfunction "DRAIN_4") (pintype "passive"))
    )
    (net (code "77") (name "RelayGenHeat") (class "Default")
      (node (ref "D61") (pin "2") (pinfunction "K_2") (pintype "passive"))
      (node (ref "J_R4") (pin "1") (pinfunction "1_1") (pintype "passive"))
      (node (ref "Q14") (pin "4") (pinfunction "DRAIN_4") (pintype "passive"))
    )
    (net (code "78") (name "RelayLOAD") (class "Default")
      (node (ref "D60") (pin "2") (pinfunction "K_2") (pintype "passive"))
      (node (ref "J_R3") (pin "1") (pinfunction "1_1") (pintype "passive"))
      (node (ref "Q13") (pin "4") (pinfunction "DRAIN_4") (pintype "passive"))
    )
    (net (code "81") (name "u_Relay1_2") (class "Default")
      (node (ref "C116") (pin "1") (pinfunction "1_1") (pintype "passive"))
      (node (ref "Opto4") (pin "2") (pintype "passive"))
    )
    (net (code "82") (name "u_Relay2_2") (class "Default")
      (node (ref "C120") (pin "1") (pinfunction "1_1") (pintype "passive"))
      (node (ref "Opto8") (pin "2") (pintype "passive"))
    )
    (net (code "83") (name "u_Relay3_2") (class "Default")
      (node (ref "C121") (pin "1") (pinfunction "1_1") (pintype "passive"))
      (node (ref "Opto9") (pin "2") (pintype "passive"))
    )
    (net (code "84") (name "u_Relay4_2") (class "Default")
      (node (ref "C122") (pin "1") (pinfunction "1_1") (pintype "passive"))
      (node (ref "Opto10") (pin "2") (pintype "passive"))
    )
    (net (code "85") (name "u_Relay5_2") (class "Default")
      (node (ref "C123") (pin "1") (pinfunction "1_1") (pintype "passive"))
      (node (ref "Opto11") (pin "2") (pintype "passive"))
    )
    (net (code "86") (name "u_RelayGEN_2") (class "Default")
      (node (ref "C18") (pin "1") (pinfunction "1_1") (pintype "passive"))
      (node (ref "Opto12") (pin "2") (pintype "passive"))
    )
    (net (code "87") (name "u_RelayGRID_N_2") (class "Default")
      (node (ref "C19") (pin "1") (pinfunction "1_1") (pintype "passive"))
      (node (ref "Opto13") (pin "2") (pintype "passive"))
    )
    (net (code "88") (name "u_RelayGRID_P_2") (class "Default")
      (node (ref "R127") (pin "2") (pinfunction "2_2") (pintype "passive"))
    )
    (net (code "89") (name "u_RelayGenHeat_2") (class "Default")
      (node (ref "C22") (pin "1") (pinfunction "1_1") (pintype "passive"))
      (node (ref "Opto15") (pin "2") (pintype "passive"))
    )
    (net (code "90") (name "u_RelayLOAD_2") (class "Default")
      (node (ref "C20") (pin "1") (pinfunction "1_1") (pintype "passive"))
      (node (ref "Opto14") (pin "2") (pintype "passive"))
    )
  )
)
